# LED_PCB_LONG.net
KiCad netlist of a schematic drawn in Altium Designer
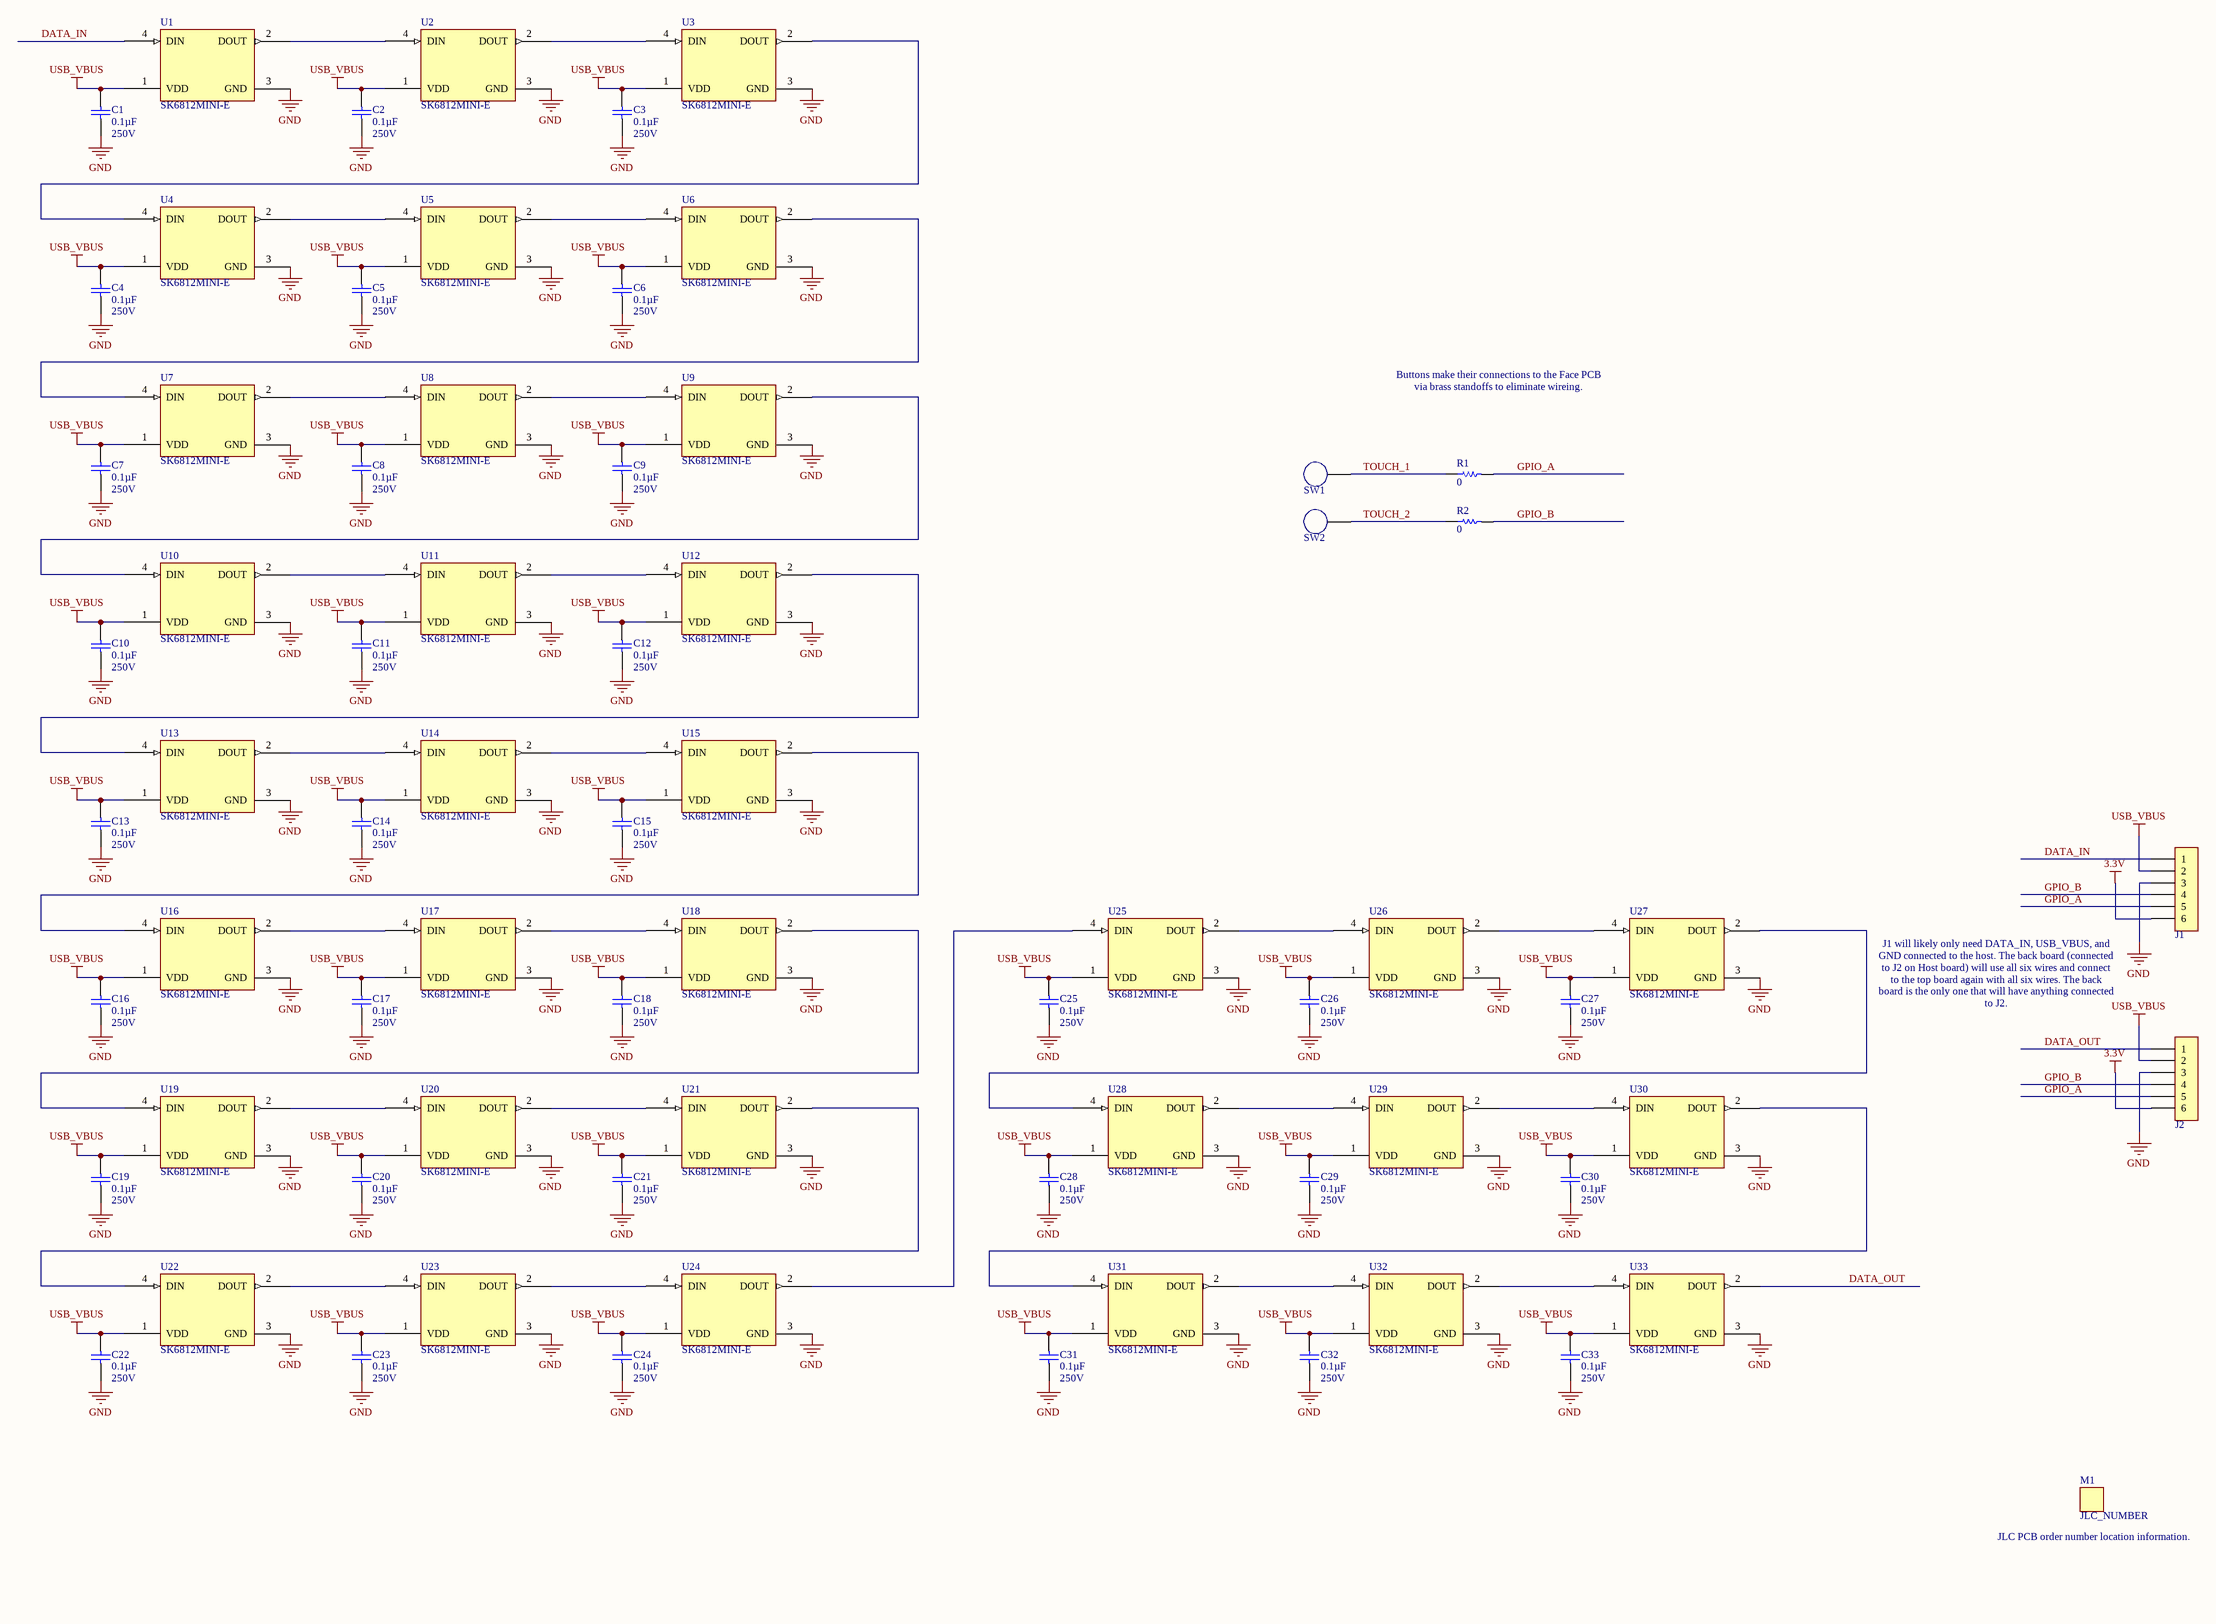
[diagram p0: LED_PCB_LONG.SchDoc]

(export (version "E")
  (design (tool "Eeschema 10.0.6"))
  (components
    (comp (ref "C1")
      (value "0.1µF")
      (footprint "Chip0805")
      (description "CAP CER 0.1UF 250V 10% X7T 0805")
      (fields
        (field (name "VOLTAGE") "250V")
        (field (name "PARTNUMBER") "C2012X7T2E104K125AA")
        (field (name "MANUFACTURER") "TDK Corporation")
      )
      (libsource (lib "Passives") (part "CAP"))
    )
    (comp (ref "C2")
      (value "0.1µF")
      (footprint "Chip0805")
      (description "CAP CER 0.1UF 250V 10% X7T 0805")
      (fields
        (field (name "VOLTAGE") "250V")
        (field (name "PARTNUMBER") "C2012X7T2E104K125AA")
        (field (name "MANUFACTURER") "TDK Corporation")
      )
      (libsource (lib "Passives") (part "CAP"))
    )
    (comp (ref "C3")
      (value "0.1µF")
      (footprint "Chip0805")
      (description "CAP CER 0.1UF 250V 10% X7T 0805")
      (fields
        (field (name "VOLTAGE") "250V")
        (field (name "PARTNUMBER") "C2012X7T2E104K125AA")
        (field (name "MANUFACTURER") "TDK Corporation")
      )
      (libsource (lib "Passives") (part "CAP"))
    )
    (comp (ref "C4")
      (value "0.1µF")
      (footprint "Chip0805")
      (description "CAP CER 0.1UF 250V 10% X7T 0805")
      (fields
        (field (name "VOLTAGE") "250V")
        (field (name "PARTNUMBER") "C2012X7T2E104K125AA")
        (field (name "MANUFACTURER") "TDK Corporation")
      )
      (libsource (lib "Passives") (part "CAP"))
    )
    (comp (ref "C5")
      (value "0.1µF")
      (footprint "Chip0805")
      (description "CAP CER 0.1UF 250V 10% X7T 0805")
      (fields
        (field (name "VOLTAGE") "250V")
        (field (name "PARTNUMBER") "C2012X7T2E104K125AA")
        (field (name "MANUFACTURER") "TDK Corporation")
      )
      (libsource (lib "Passives") (part "CAP"))
    )
    (comp (ref "C6")
      (value "0.1µF")
      (footprint "Chip0805")
      (description "CAP CER 0.1UF 250V 10% X7T 0805")
      (fields
        (field (name "VOLTAGE") "250V")
        (field (name "PARTNUMBER") "C2012X7T2E104K125AA")
        (field (name "MANUFACTURER") "TDK Corporation")
      )
      (libsource (lib "Passives") (part "CAP"))
    )
    (comp (ref "C7")
      (value "0.1µF")
      (footprint "Chip0805")
      (description "CAP CER 0.1UF 250V 10% X7T 0805")
      (fields
        (field (name "VOLTAGE") "250V")
        (field (name "PARTNUMBER") "C2012X7T2E104K125AA")
        (field (name "MANUFACTURER") "TDK Corporation")
      )
      (libsource (lib "Passives") (part "CAP"))
    )
    (comp (ref "C8")
      (value "0.1µF")
      (footprint "Chip0805")
      (description "CAP CER 0.1UF 250V 10% X7T 0805")
      (fields
        (field (name "VOLTAGE") "250V")
        (field (name "PARTNUMBER") "C2012X7T2E104K125AA")
        (field (name "MANUFACTURER") "TDK Corporation")
      )
      (libsource (lib "Passives") (part "CAP"))
    )
    (comp (ref "C9")
      (value "0.1µF")
      (footprint "Chip0805")
      (description "CAP CER 0.1UF 250V 10% X7T 0805")
      (fields
        (field (name "VOLTAGE") "250V")
        (field (name "PARTNUMBER") "C2012X7T2E104K125AA")
        (field (name "MANUFACTURER") "TDK Corporation")
      )
      (libsource (lib "Passives") (part "CAP"))
    )
    (comp (ref "C10")
      (value "0.1µF")
      (footprint "Chip0805")
      (description "CAP CER 0.1UF 250V 10% X7T 0805")
      (fields
        (field (name "VOLTAGE") "250V")
        (field (name "PARTNUMBER") "C2012X7T2E104K125AA")
        (field (name "MANUFACTURER") "TDK Corporation")
      )
      (libsource (lib "Passives") (part "CAP"))
    )
    (comp (ref "C11")
      (value "0.1µF")
      (footprint "Chip0805")
      (description "CAP CER 0.1UF 250V 10% X7T 0805")
      (fields
        (field (name "VOLTAGE") "250V")
        (field (name "PARTNUMBER") "C2012X7T2E104K125AA")
        (field (name "MANUFACTURER") "TDK Corporation")
      )
      (libsource (lib "Passives") (part "CAP"))
    )
    (comp (ref "C12")
      (value "0.1µF")
      (footprint "Chip0805")
      (description "CAP CER 0.1UF 250V 10% X7T 0805")
      (fields
        (field (name "VOLTAGE") "250V")
        (field (name "PARTNUMBER") "C2012X7T2E104K125AA")
        (field (name "MANUFACTURER") "TDK Corporation")
      )
      (libsource (lib "Passives") (part "CAP"))
    )
    (comp (ref "C13")
      (value "0.1µF")
      (footprint "Chip0805")
      (description "CAP CER 0.1UF 250V 10% X7T 0805")
      (fields
        (field (name "VOLTAGE") "250V")
        (field (name "PARTNUMBER") "C2012X7T2E104K125AA")
        (field (name "MANUFACTURER") "TDK Corporation")
      )
      (libsource (lib "Passives") (part "CAP"))
    )
    (comp (ref "C14")
      (value "0.1µF")
      (footprint "Chip0805")
      (description "CAP CER 0.1UF 250V 10% X7T 0805")
      (fields
        (field (name "VOLTAGE") "250V")
        (field (name "PARTNUMBER") "C2012X7T2E104K125AA")
        (field (name "MANUFACTURER") "TDK Corporation")
      )
      (libsource (lib "Passives") (part "CAP"))
    )
    (comp (ref "C15")
      (value "0.1µF")
      (footprint "Chip0805")
      (description "CAP CER 0.1UF 250V 10% X7T 0805")
      (fields
        (field (name "VOLTAGE") "250V")
        (field (name "PARTNUMBER") "C2012X7T2E104K125AA")
        (field (name "MANUFACTURER") "TDK Corporation")
      )
      (libsource (lib "Passives") (part "CAP"))
    )
    (comp (ref "C16")
      (value "0.1µF")
      (footprint "Chip0805")
      (description "CAP CER 0.1UF 250V 10% X7T 0805")
      (fields
        (field (name "VOLTAGE") "250V")
        (field (name "PARTNUMBER") "C2012X7T2E104K125AA")
        (field (name "MANUFACTURER") "TDK Corporation")
      )
      (libsource (lib "Passives") (part "CAP"))
    )
    (comp (ref "C17")
      (value "0.1µF")
      (footprint "Chip0805")
      (description "CAP CER 0.1UF 250V 10% X7T 0805")
      (fields
        (field (name "VOLTAGE") "250V")
        (field (name "PARTNUMBER") "C2012X7T2E104K125AA")
        (field (name "MANUFACTURER") "TDK Corporation")
      )
      (libsource (lib "Passives") (part "CAP"))
    )
    (comp (ref "C18")
      (value "0.1µF")
      (footprint "Chip0805")
      (description "CAP CER 0.1UF 250V 10% X7T 0805")
      (fields
        (field (name "VOLTAGE") "250V")
        (field (name "PARTNUMBER") "C2012X7T2E104K125AA")
        (field (name "MANUFACTURER") "TDK Corporation")
      )
      (libsource (lib "Passives") (part "CAP"))
    )
    (comp (ref "C19")
      (value "0.1µF")
      (footprint "Chip0805")
      (description "CAP CER 0.1UF 250V 10% X7T 0805")
      (fields
        (field (name "VOLTAGE") "250V")
        (field (name "PARTNUMBER") "C2012X7T2E104K125AA")
        (field (name "MANUFACTURER") "TDK Corporation")
      )
      (libsource (lib "Passives") (part "CAP"))
    )
    (comp (ref "C20")
      (value "0.1µF")
      (footprint "Chip0805")
      (description "CAP CER 0.1UF 250V 10% X7T 0805")
      (fields
        (field (name "VOLTAGE") "250V")
        (field (name "PARTNUMBER") "C2012X7T2E104K125AA")
        (field (name "MANUFACTURER") "TDK Corporation")
      )
      (libsource (lib "Passives") (part "CAP"))
    )
    (comp (ref "C21")
      (value "0.1µF")
      (footprint "Chip0805")
      (description "CAP CER 0.1UF 250V 10% X7T 0805")
      (fields
        (field (name "VOLTAGE") "250V")
        (field (name "PARTNUMBER") "C2012X7T2E104K125AA")
        (field (name "MANUFACTURER") "TDK Corporation")
      )
      (libsource (lib "Passives") (part "CAP"))
    )
    (comp (ref "C22")
      (value "0.1µF")
      (footprint "Chip0805")
      (description "CAP CER 0.1UF 250V 10% X7T 0805")
      (fields
        (field (name "VOLTAGE") "250V")
        (field (name "PARTNUMBER") "C2012X7T2E104K125AA")
        (field (name "MANUFACTURER") "TDK Corporation")
      )
      (libsource (lib "Passives") (part "CAP"))
    )
    (comp (ref "C23")
      (value "0.1µF")
      (footprint "Chip0805")
      (description "CAP CER 0.1UF 250V 10% X7T 0805")
      (fields
        (field (name "VOLTAGE") "250V")
        (field (name "PARTNUMBER") "C2012X7T2E104K125AA")
        (field (name "MANUFACTURER") "TDK Corporation")
      )
      (libsource (lib "Passives") (part "CAP"))
    )
    (comp (ref "C24")
      (value "0.1µF")
      (footprint "Chip0805")
      (description "CAP CER 0.1UF 250V 10% X7T 0805")
      (fields
        (field (name "VOLTAGE") "250V")
        (field (name "PARTNUMBER") "C2012X7T2E104K125AA")
        (field (name "MANUFACTURER") "TDK Corporation")
      )
      (libsource (lib "Passives") (part "CAP"))
    )
    (comp (ref "C25")
      (value "0.1µF")
      (footprint "Chip0805")
      (description "CAP CER 0.1UF 250V 10% X7T 0805")
      (fields
        (field (name "VOLTAGE") "250V")
        (field (name "PARTNUMBER") "C2012X7T2E104K125AA")
        (field (name "MANUFACTURER") "TDK Corporation")
      )
      (libsource (lib "Passives") (part "CAP"))
    )
    (comp (ref "C26")
      (value "0.1µF")
      (footprint "Chip0805")
      (description "CAP CER 0.1UF 250V 10% X7T 0805")
      (fields
        (field (name "VOLTAGE") "250V")
        (field (name "PARTNUMBER") "C2012X7T2E104K125AA")
        (field (name "MANUFACTURER") "TDK Corporation")
      )
      (libsource (lib "Passives") (part "CAP"))
    )
    (comp (ref "C27")
      (value "0.1µF")
      (footprint "Chip0805")
      (description "CAP CER 0.1UF 250V 10% X7T 0805")
      (fields
        (field (name "VOLTAGE") "250V")
        (field (name "PARTNUMBER") "C2012X7T2E104K125AA")
        (field (name "MANUFACTURER") "TDK Corporation")
      )
      (libsource (lib "Passives") (part "CAP"))
    )
    (comp (ref "C28")
      (value "0.1µF")
      (footprint "Chip0805")
      (description "CAP CER 0.1UF 250V 10% X7T 0805")
      (fields
        (field (name "VOLTAGE") "250V")
        (field (name "PARTNUMBER") "C2012X7T2E104K125AA")
        (field (name "MANUFACTURER") "TDK Corporation")
      )
      (libsource (lib "Passives") (part "CAP"))
    )
    (comp (ref "C29")
      (value "0.1µF")
      (footprint "Chip0805")
      (description "CAP CER 0.1UF 250V 10% X7T 0805")
      (fields
        (field (name "VOLTAGE") "250V")
        (field (name "PARTNUMBER") "C2012X7T2E104K125AA")
        (field (name "MANUFACTURER") "TDK Corporation")
      )
      (libsource (lib "Passives") (part "CAP"))
    )
    (comp (ref "C30")
      (value "0.1µF")
      (footprint "Chip0805")
      (description "CAP CER 0.1UF 250V 10% X7T 0805")
      (fields
        (field (name "VOLTAGE") "250V")
        (field (name "PARTNUMBER") "C2012X7T2E104K125AA")
        (field (name "MANUFACTURER") "TDK Corporation")
      )
      (libsource (lib "Passives") (part "CAP"))
    )
    (comp (ref "C31")
      (value "0.1µF")
      (footprint "Chip0805")
      (description "CAP CER 0.1UF 250V 10% X7T 0805")
      (fields
        (field (name "VOLTAGE") "250V")
        (field (name "PARTNUMBER") "C2012X7T2E104K125AA")
        (field (name "MANUFACTURER") "TDK Corporation")
      )
      (libsource (lib "Passives") (part "CAP"))
    )
    (comp (ref "C32")
      (value "0.1µF")
      (footprint "Chip0805")
      (description "CAP CER 0.1UF 250V 10% X7T 0805")
      (fields
        (field (name "VOLTAGE") "250V")
        (field (name "PARTNUMBER") "C2012X7T2E104K125AA")
        (field (name "MANUFACTURER") "TDK Corporation")
      )
      (libsource (lib "Passives") (part "CAP"))
    )
    (comp (ref "C33")
      (value "0.1µF")
      (footprint "Chip0805")
      (description "CAP CER 0.1UF 250V 10% X7T 0805")
      (fields
        (field (name "VOLTAGE") "250V")
        (field (name "PARTNUMBER") "C2012X7T2E104K125AA")
        (field (name "MANUFACTURER") "TDK Corporation")
      )
      (libsource (lib "Passives") (part "CAP"))
    )
    (comp (ref "J1")
      (value "HEADER_1x6_NO_BOM")
      (footprint "HEADER_1x6_100mil_NP")
      (libsource (lib "Mechanical") (part "HEADER_1x6_NO_BOM"))
    )
    (comp (ref "J2")
      (value "HEADER_1x6_NO_BOM")
      (footprint "HEADER_1x6_100mil_NP")
      (libsource (lib "Mechanical") (part "HEADER_1x6_NO_BOM"))
    )
    (comp (ref "M1")
      (value "JLC_NUMBER")
      (footprint "JLC_NUMBER")
      (description "JLC Order Number Location")
      (libsource (lib "Mechanical") (part "MECH_NO_BOM"))
    )
    (comp (ref "R1")
      (value "0")
      (footprint "Chip0805")
      (description "RES 0.0 OHM 1/8W JUMP 0805 SMD")
      (fields (field (name "PARTNUMBER") "CRCW08050000Z0EA") (field (name "MANUFACTURER") "Vishay Dale"))
      (libsource (lib "Passives") (part "RES"))
    )
    (comp (ref "R2")
      (value "0")
      (footprint "Chip0805")
      (description "RES 0.0 OHM 1/8W JUMP 0805 SMD")
      (fields (field (name "PARTNUMBER") "CRCW08050000Z0EA") (field (name "MANUFACTURER") "Vishay Dale"))
      (libsource (lib "Passives") (part "RES"))
    )
    (comp (ref "SW1")
      (value "TOUCH_PAD_NO_BOM")
      (footprint "TENTED_PAD_5mil")
      (libsource (lib "Mechanical") (part "TOUCH_PAD_NO_BOM"))
    )
    (comp (ref "SW2")
      (value "TOUCH_PAD_NO_BOM")
      (footprint "TENTED_PAD_5mil")
      (libsource (lib "Mechanical") (part "TOUCH_PAD_NO_BOM"))
    )
    (comp (ref "U1")
      (value "SK6812MINI-E")
      (footprint "SK6812MINI-E")
      (description "Addressable RGB LED")
      (fields (field (name "MANUFACTURER") "Adafruit Industries LLC"))
      (libsource (lib "Optoelectronics") (part "SK6812MINI-E"))
    )
    (comp (ref "U2")
      (value "SK6812MINI-E")
      (footprint "SK6812MINI-E")
      (description "Addressable RGB LED")
      (fields (field (name "MANUFACTURER") "Adafruit Industries LLC"))
      (libsource (lib "Optoelectronics") (part "SK6812MINI-E"))
    )
    (comp (ref "U3")
      (value "SK6812MINI-E")
      (footprint "SK6812MINI-E")
      (description "Addressable RGB LED")
      (fields (field (name "MANUFACTURER") "Adafruit Industries LLC"))
      (libsource (lib "Optoelectronics") (part "SK6812MINI-E"))
    )
    (comp (ref "U4")
      (value "SK6812MINI-E")
      (footprint "SK6812MINI-E")
      (description "Addressable RGB LED")
      (fields (field (name "MANUFACTURER") "Adafruit Industries LLC"))
      (libsource (lib "Optoelectronics") (part "SK6812MINI-E"))
    )
    (comp (ref "U5")
      (value "SK6812MINI-E")
      (footprint "SK6812MINI-E")
      (description "Addressable RGB LED")
      (fields (field (name "MANUFACTURER") "Adafruit Industries LLC"))
      (libsource (lib "Optoelectronics") (part "SK6812MINI-E"))
    )
    (comp (ref "U6")
      (value "SK6812MINI-E")
      (footprint "SK6812MINI-E")
      (description "Addressable RGB LED")
      (fields (field (name "MANUFACTURER") "Adafruit Industries LLC"))
      (libsource (lib "Optoelectronics") (part "SK6812MINI-E"))
    )
    (comp (ref "U7")
      (value "SK6812MINI-E")
      (footprint "SK6812MINI-E")
      (description "Addressable RGB LED")
      (fields (field (name "MANUFACTURER") "Adafruit Industries LLC"))
      (libsource (lib "Optoelectronics") (part "SK6812MINI-E"))
    )
    (comp (ref "U8")
      (value "SK6812MINI-E")
      (footprint "SK6812MINI-E")
      (description "Addressable RGB LED")
      (fields (field (name "MANUFACTURER") "Adafruit Industries LLC"))
      (libsource (lib "Optoelectronics") (part "SK6812MINI-E"))
    )
    (comp (ref "U9")
      (value "SK6812MINI-E")
      (footprint "SK6812MINI-E")
      (description "Addressable RGB LED")
      (fields (field (name "MANUFACTURER") "Adafruit Industries LLC"))
      (libsource (lib "Optoelectronics") (part "SK6812MINI-E"))
    )
    (comp (ref "U10")
      (value "SK6812MINI-E")
      (footprint "SK6812MINI-E")
      (description "Addressable RGB LED")
      (fields (field (name "MANUFACTURER") "Adafruit Industries LLC"))
      (libsource (lib "Optoelectronics") (part "SK6812MINI-E"))
    )
    (comp (ref "U11")
      (value "SK6812MINI-E")
      (footprint "SK6812MINI-E")
      (description "Addressable RGB LED")
      (fields (field (name "MANUFACTURER") "Adafruit Industries LLC"))
      (libsource (lib "Optoelectronics") (part "SK6812MINI-E"))
    )
    (comp (ref "U12")
      (value "SK6812MINI-E")
      (footprint "SK6812MINI-E")
      (description "Addressable RGB LED")
      (fields (field (name "MANUFACTURER") "Adafruit Industries LLC"))
      (libsource (lib "Optoelectronics") (part "SK6812MINI-E"))
    )
    (comp (ref "U13")
      (value "SK6812MINI-E")
      (footprint "SK6812MINI-E")
      (description "Addressable RGB LED")
      (fields (field (name "MANUFACTURER") "Adafruit Industries LLC"))
      (libsource (lib "Optoelectronics") (part "SK6812MINI-E"))
    )
    (comp (ref "U14")
      (value "SK6812MINI-E")
      (footprint "SK6812MINI-E")
      (description "Addressable RGB LED")
      (fields (field (name "MANUFACTURER") "Adafruit Industries LLC"))
      (libsource (lib "Optoelectronics") (part "SK6812MINI-E"))
    )
    (comp (ref "U15")
      (value "SK6812MINI-E")
      (footprint "SK6812MINI-E")
      (description "Addressable RGB LED")
      (fields (field (name "MANUFACTURER") "Adafruit Industries LLC"))
      (libsource (lib "Optoelectronics") (part "SK6812MINI-E"))
    )
    (comp (ref "U16")
      (value "SK6812MINI-E")
      (footprint "SK6812MINI-E")
      (description "Addressable RGB LED")
      (fields (field (name "MANUFACTURER") "Adafruit Industries LLC"))
      (libsource (lib "Optoelectronics") (part "SK6812MINI-E"))
    )
    (comp (ref "U17")
      (value "SK6812MINI-E")
      (footprint "SK6812MINI-E")
      (description "Addressable RGB LED")
      (fields (field (name "MANUFACTURER") "Adafruit Industries LLC"))
      (libsource (lib "Optoelectronics") (part "SK6812MINI-E"))
    )
    (comp (ref "U18")
      (value "SK6812MINI-E")
      (footprint "SK6812MINI-E")
      (description "Addressable RGB LED")
      (fields (field (name "MANUFACTURER") "Adafruit Industries LLC"))
      (libsource (lib "Optoelectronics") (part "SK6812MINI-E"))
    )
    (comp (ref "U19")
      (value "SK6812MINI-E")
      (footprint "SK6812MINI-E")
      (description "Addressable RGB LED")
      (fields (field (name "MANUFACTURER") "Adafruit Industries LLC"))
      (libsource (lib "Optoelectronics") (part "SK6812MINI-E"))
    )
    (comp (ref "U20")
      (value "SK6812MINI-E")
      (footprint "SK6812MINI-E")
      (description "Addressable RGB LED")
      (fields (field (name "MANUFACTURER") "Adafruit Industries LLC"))
      (libsource (lib "Optoelectronics") (part "SK6812MINI-E"))
    )
    (comp (ref "U21")
      (value "SK6812MINI-E")
      (footprint "SK6812MINI-E")
      (description "Addressable RGB LED")
      (fields (field (name "MANUFACTURER") "Adafruit Industries LLC"))
      (libsource (lib "Optoelectronics") (part "SK6812MINI-E"))
    )
    (comp (ref "U22")
      (value "SK6812MINI-E")
      (footprint "SK6812MINI-E")
      (description "Addressable RGB LED")
      (fields (field (name "MANUFACTURER") "Adafruit Industries LLC"))
      (libsource (lib "Optoelectronics") (part "SK6812MINI-E"))
    )
    (comp (ref "U23")
      (value "SK6812MINI-E")
      (footprint "SK6812MINI-E")
      (description "Addressable RGB LED")
      (fields (field (name "MANUFACTURER") "Adafruit Industries LLC"))
      (libsource (lib "Optoelectronics") (part "SK6812MINI-E"))
    )
    (comp (ref "U24")
      (value "SK6812MINI-E")
      (footprint "SK6812MINI-E")
      (description "Addressable RGB LED")
      (fields (field (name "MANUFACTURER") "Adafruit Industries LLC"))
      (libsource (lib "Optoelectronics") (part "SK6812MINI-E"))
    )
    (comp (ref "U25")
      (value "SK6812MINI-E")
      (footprint "SK6812MINI-E")
      (description "Addressable RGB LED")
      (fields (field (name "MANUFACTURER") "Adafruit Industries LLC"))
      (libsource (lib "Optoelectronics") (part "SK6812MINI-E"))
    )
    (comp (ref "U26")
      (value "SK6812MINI-E")
      (footprint "SK6812MINI-E")
      (description "Addressable RGB LED")
      (fields (field (name "MANUFACTURER") "Adafruit Industries LLC"))
      (libsource (lib "Optoelectronics") (part "SK6812MINI-E"))
    )
    (comp (ref "U27")
      (value "SK6812MINI-E")
      (footprint "SK6812MINI-E")
      (description "Addressable RGB LED")
      (fields (field (name "MANUFACTURER") "Adafruit Industries LLC"))
      (libsource (lib "Optoelectronics") (part "SK6812MINI-E"))
    )
    (comp (ref "U28")
      (value "SK6812MINI-E")
      (footprint "SK6812MINI-E")
      (description "Addressable RGB LED")
      (fields (field (name "MANUFACTURER") "Adafruit Industries LLC"))
      (libsource (lib "Optoelectronics") (part "SK6812MINI-E"))
    )
    (comp (ref "U29")
      (value "SK6812MINI-E")
      (footprint "SK6812MINI-E")
      (description "Addressable RGB LED")
      (fields (field (name "MANUFACTURER") "Adafruit Industries LLC"))
      (libsource (lib "Optoelectronics") (part "SK6812MINI-E"))
    )
    (comp (ref "U30")
      (value "SK6812MINI-E")
      (footprint "SK6812MINI-E")
      (description "Addressable RGB LED")
      (fields (field (name "MANUFACTURER") "Adafruit Industries LLC"))
      (libsource (lib "Optoelectronics") (part "SK6812MINI-E"))
    )
    (comp (ref "U31")
      (value "SK6812MINI-E")
      (footprint "SK6812MINI-E")
      (description "Addressable RGB LED")
      (fields (field (name "MANUFACTURER") "Adafruit Industries LLC"))
      (libsource (lib "Optoelectronics") (part "SK6812MINI-E"))
    )
    (comp (ref "U32")
      (value "SK6812MINI-E")
      (footprint "SK6812MINI-E")
      (description "Addressable RGB LED")
      (fields (field (name "MANUFACTURER") "Adafruit Industries LLC"))
      (libsource (lib "Optoelectronics") (part "SK6812MINI-E"))
    )
    (comp (ref "U33")
      (value "SK6812MINI-E")
      (footprint "SK6812MINI-E")
      (description "Addressable RGB LED")
      (fields (field (name "MANUFACTURER") "Adafruit Industries LLC"))
      (libsource (lib "Optoelectronics") (part "SK6812MINI-E"))
    )
  )
  (nets
    (net (code "1") (name "/DATA_IN") (class "Default")
      (node (ref "J1") (pin "1") (pinfunction "1_1") (pintype "passive"))
      (node (ref "U1") (pin "4") (pinfunction "DIN_4") (pintype "input"))
    )
    (net (code "2") (name "/DATA_OUT") (class "Default")
      (node (ref "J2") (pin "1") (pinfunction "1_1") (pintype "passive"))
      (node (ref "U33") (pin "2") (pinfunction "DOUT_2") (pintype "output"))
    )
    (net (code "3") (name "/GPIO_A") (class "Default")
      (node (ref "J1") (pin "5") (pinfunction "5_5") (pintype "passive"))
      (node (ref "J2") (pin "5") (pinfunction "5_5") (pintype "passive"))
      (node (ref "R1") (pin "2") (pinfunction "2_2") (pintype "passive"))
    )
    (net (code "4") (name "/GPIO_B") (class "Default")
      (node (ref "J1") (pin "4") (pinfunction "4_4") (pintype "passive"))
      (node (ref "J2") (pin "4") (pinfunction "4_4") (pintype "passive"))
      (node (ref "R2") (pin "2") (pinfunction "2_2") (pintype "passive"))
    )
    (net (code "5") (name "/TOUCH_1") (class "Default")
      (node (ref "R1") (pin "1") (pinfunction "1_1") (pintype "passive"))
      (node (ref "SW1") (pin "1") (pinfunction "1_1") (pintype "passive"))
    )
    (net (code "6") (name "/TOUCH_2") (class "Default")
      (node (ref "R2") (pin "1") (pinfunction "1_1") (pintype "passive"))
      (node (ref "SW2") (pin "1") (pinfunction "1_1") (pintype "passive"))
    )
    (net (code "7") (name "3.3V") (class "Default")
      (node (ref "J1") (pin "6") (pinfunction "6_6") (pintype "passive"))
      (node (ref "J2") (pin "6") (pinfunction "6_6") (pintype "passive"))
    )
    (net (code "8") (name "GND") (class "Default")
      (node (ref "C1") (pin "1") (pinfunction "1_1") (pintype "passive"))
      (node (ref "C10") (pin "1") (pinfunction "1_1") (pintype "passive"))
      (node (ref "C11") (pin "1") (pinfunction "1_1") (pintype "passive"))
      (node (ref "C12") (pin "1") (pinfunction "1_1") (pintype "passive"))
      (node (ref "C13") (pin "1") (pinfunction "1_1") (pintype "passive"))
      (node (ref "C14") (pin "1") (pinfunction "1_1") (pintype "passive"))
      (node (ref "C15") (pin "1") (pinfunction "1_1") (pintype "passive"))
      (node (ref "C16") (pin "1") (pinfunction "1_1") (pintype "passive"))
      (node (ref "C17") (pin "1") (pinfunction "1_1") (pintype "passive"))
      (node (ref "C18") (pin "1") (pinfunction "1_1") (pintype "passive"))
      (node (ref "C19") (pin "1") (pinfunction "1_1") (pintype "passive"))
      (node (ref "C2") (pin "1") (pinfunction "1_1") (pintype "passive"))
      (node (ref "C20") (pin "1") (pinfunction "1_1") (pintype "passive"))
      (node (ref "C21") (pin "1") (pinfunction "1_1") (pintype "passive"))
      (node (ref "C22") (pin "1") (pinfunction "1_1") (pintype "passive"))
      (node (ref "C23") (pin "1") (pinfunction "1_1") (pintype "passive"))
      (node (ref "C24") (pin "1") (pinfunction "1_1") (pintype "passive"))
      (node (ref "C25") (pin "1") (pinfunction "1_1") (pintype "passive"))
      (node (ref "C26") (pin "1") (pinfunction "1_1") (pintype "passive"))
      (node (ref "C27") (pin "1") (pinfunction "1_1") (pintype "passive"))
      (node (ref "C28") (pin "1") (pinfunction "1_1") (pintype "passive"))
      (node (ref "C29") (pin "1") (pinfunction "1_1") (pintype "passive"))
      (node (ref "C3") (pin "1") (pinfunction "1_1") (pintype "passive"))
      (node (ref "C30") (pin "1") (pinfunction "1_1") (pintype "passive"))
      (node (ref "C31") (pin "1") (pinfunction "1_1") (pintype "passive"))
      (node (ref "C32") (pin "1") (pinfunction "1_1") (pintype "passive"))
      (node (ref "C33") (pin "1") (pinfunction "1_1") (pintype "passive"))
      (node (ref "C4") (pin "1") (pinfunction "1_1") (pintype "passive"))
      (node (ref "C5") (pin "1") (pinfunction "1_1") (pintype "passive"))
      (node (ref "C6") (pin "1") (pinfunction "1_1") (pintype "passive"))
      (node (ref "C7") (pin "1") (pinfunction "1_1") (pintype "passive"))
      (node (ref "C8") (pin "1") (pinfunction "1_1") (pintype "passive"))
      (node (ref "C9") (pin "1") (pinfunction "1_1") (pintype "passive"))
      (node (ref "J1") (pin "3") (pinfunction "3_3") (pintype "passive"))
      (node (ref "J2") (pin "3") (pinfunction "3_3") (pintype "passive"))
      (node (ref "U1") (pin "3") (pinfunction "GND_3") (pintype "passive"))
      (node (ref "U10") (pin "3") (pinfunction "GND_3") (pintype "passive"))
      (node (ref "U11") (pin "3") (pinfunction "GND_3") (pintype "passive"))
      (node (ref "U12") (pin "3") (pinfunction "GND_3") (pintype "passive"))
      (node (ref "U13") (pin "3") (pinfunction "GND_3") (pintype "passive"))
      (node (ref "U14") (pin "3") (pinfunction "GND_3") (pintype "passive"))
      (node (ref "U15") (pin "3") (pinfunction "GND_3") (pintype "passive"))
      (node (ref "U16") (pin "3") (pinfunction "GND_3") (pintype "passive"))
      (node (ref "U17") (pin "3") (pinfunction "GND_3") (pintype "passive"))
      (node (ref "U18") (pin "3") (pinfunction "GND_3") (pintype "passive"))
      (node (ref "U19") (pin "3") (pinfunction "GND_3") (pintype "passive"))
      (node (ref "U2") (pin "3") (pinfunction "GND_3") (pintype "passive"))
      (node (ref "U20") (pin "3") (pinfunction "GND_3") (pintype "passive"))
      (node (ref "U21") (pin "3") (pinfunction "GND_3") (pintype "passive"))
      (node (ref "U22") (pin "3") (pinfunction "GND_3") (pintype "passive"))
      (node (ref "U23") (pin "3") (pinfunction "GND_3") (pintype "passive"))
      (node (ref "U24") (pin "3") (pinfunction "GND_3") (pintype "passive"))
      (node (ref "U25") (pin "3") (pinfunction "GND_3") (pintype "passive"))
      (node (ref "U26") (pin "3") (pinfunction "GND_3") (pintype "passive"))
      (node (ref "U27") (pin "3") (pinfunction "GND_3") (pintype "passive"))
      (node (ref "U28") (pin "3") (pinfunction "GND_3") (pintype "passive"))
      (node (ref "U29") (pin "3") (pinfunction "GND_3") (pintype "passive"))
      (node (ref "U3") (pin "3") (pinfunction "GND_3") (pintype "passive"))
      (node (ref "U30") (pin "3") (pinfunction "GND_3") (pintype "passive"))
      (node (ref "U31") (pin "3") (pinfunction "GND_3") (pintype "passive"))
      (node (ref "U32") (pin "3") (pinfunction "GND_3") (pintype "passive"))
      (node (ref "U33") (pin "3") (pinfunction "GND_3") (pintype "passive"))
      (node (ref "U4") (pin "3") (pinfunction "GND_3") (pintype "passive"))
      (node (ref "U5") (pin "3") (pinfunction "GND_3") (pintype "passive"))
      (node (ref "U6") (pin "3") (pinfunction "GND_3") (pintype "passive"))
      (node (ref "U7") (pin "3") (pinfunction "GND_3") (pintype "passive"))
      (node (ref "U8") (pin "3") (pinfunction "GND_3") (pintype "passive"))
      (node (ref "U9") (pin "3") (pinfunction "GND_3") (pintype "passive"))
    )
    (net (code "9") (name "Net-(U1-DOUT)") (class "Default")
      (node (ref "U1") (pin "2") (pinfunction "DOUT_2") (pintype "output"))
      (node (ref "U2") (pin "4") (pinfunction "DIN_4") (pintype "input"))
    )
    (net (code "10") (name "Net-(U2-DOUT)") (class "Default")
      (node (ref "U2") (pin "2") (pinfunction "DOUT_2") (pintype "output"))
      (node (ref "U3") (pin "4") (pinfunction "DIN_4") (pintype "input"))
    )
    (net (code "11") (name "Net-(U3-DOUT)") (class "Default")
      (node (ref "U3") (pin "2") (pinfunction "DOUT_2") (pintype "output"))
      (node (ref "U4") (pin "4") (pinfunction "DIN_4") (pintype "input"))
    )
    (net (code "12") (name "Net-(U4-DOUT)") (class "Default")
      (node (ref "U4") (pin "2") (pinfunction "DOUT_2") (pintype "output"))
      (node (ref "U5") (pin "4") (pinfunction "DIN_4") (pintype "input"))
    )
    (net (code "13") (name "Net-(U5-DOUT)") (class "Default")
      (node (ref "U5") (pin "2") (pinfunction "DOUT_2") (pintype "output"))
      (node (ref "U6") (pin "4") (pinfunction "DIN_4") (pintype "input"))
    )
    (net (code "14") (name "Net-(U6-DOUT)") (class "Default")
      (node (ref "U6") (pin "2") (pinfunction "DOUT_2") (pintype "output"))
      (node (ref "U7") (pin "4") (pinfunction "DIN_4") (pintype "input"))
    )
    (net (code "15") (name "Net-(U7-DOUT)") (class "Default")
      (node (ref "U7") (pin "2") (pinfunction "DOUT_2") (pintype "output"))
      (node (ref "U8") (pin "4") (pinfunction "DIN_4") (pintype "input"))
    )
    (net (code "16") (name "Net-(U8-DOUT)") (class "Default")
      (node (ref "U8") (pin "2") (pinfunction "DOUT_2") (pintype "output"))
      (node (ref "U9") (pin "4") (pinfunction "DIN_4") (pintype "input"))
    )
    (net (code "17") (name "Net-(U10-DIN)") (class "Default")
      (node (ref "U10") (pin "4") (pinfunction "DIN_4") (pintype "input"))
      (node (ref "U9") (pin "2") (pinfunction "DOUT_2") (pintype "output"))
    )
    (net (code "18") (name "Net-(U10-DOUT)") (class "Default")
      (node (ref "U10") (pin "2") (pinfunction "DOUT_2") (pintype "output"))
      (node (ref "U11") (pin "4") (pinfunction "DIN_4") (pintype "input"))
    )
    (net (code "19") (name "Net-(U11-DOUT)") (class "Default")
      (node (ref "U11") (pin "2") (pinfunction "DOUT_2") (pintype "output"))
      (node (ref "U12") (pin "4") (pinfunction "DIN_4") (pintype "input"))
    )
    (net (code "20") (name "Net-(U12-DOUT)") (class "Default")
      (node (ref "U12") (pin "2") (pinfunction "DOUT_2") (pintype "output"))
      (node (ref "U13") (pin "4") (pinfunction "DIN_4") (pintype "input"))
    )
    (net (code "21") (name "Net-(U13-DOUT)") (class "Default")
      (node (ref "U13") (pin "2") (pinfunction "DOUT_2") (pintype "output"))
      (node (ref "U14") (pin "4") (pinfunction "DIN_4") (pintype "input"))
    )
    (net (code "22") (name "Net-(U14-DOUT)") (class "Default")
      (node (ref "U14") (pin "2") (pinfunction "DOUT_2") (pintype "output"))
      (node (ref "U15") (pin "4") (pinfunction "DIN_4") (pintype "input"))
    )
    (net (code "23") (name "Net-(U15-DOUT)") (class "Default")
      (node (ref "U15") (pin "2") (pinfunction "DOUT_2") (pintype "output"))
      (node (ref "U16") (pin "4") (pinfunction "DIN_4") (pintype "input"))
    )
    (net (code "24") (name "Net-(U16-DOUT)") (class "Default")
      (node (ref "U16") (pin "2") (pinfunction "DOUT_2") (pintype "output"))
      (node (ref "U17") (pin "4") (pinfunction "DIN_4") (pintype "input"))
    )
    (net (code "25") (name "Net-(U17-DOUT)") (class "Default")
      (node (ref "U17") (pin "2") (pinfunction "DOUT_2") (pintype "output"))
      (node (ref "U18") (pin "4") (pinfunction "DIN_4") (pintype "input"))
    )
    (net (code "26") (name "Net-(U18-DOUT)") (class "Default")
      (node (ref "U18") (pin "2") (pinfunction "DOUT_2") (pintype "output"))
      (node (ref "U19") (pin "4") (pinfunction "DIN_4") (pintype "input"))
    )
    (net (code "27") (name "Net-(U19-DOUT)") (class "Default")
      (node (ref "U19") (pin "2") (pinfunction "DOUT_2") (pintype "output"))
      (node (ref "U20") (pin "4") (pinfunction "DIN_4") (pintype "input"))
    )
    (net (code "28") (name "Net-(U20-DOUT)") (class "Default")
      (node (ref "U20") (pin "2") (pinfunction "DOUT_2") (pintype "output"))
      (node (ref "U21") (pin "4") (pinfunction "DIN_4") (pintype "input"))
    )
    (net (code "29") (name "Net-(U21-DOUT)") (class "Default")
      (node (ref "U21") (pin "2") (pinfunction "DOUT_2") (pintype "output"))
      (node (ref "U22") (pin "4") (pinfunction "DIN_4") (pintype "input"))
    )
    (net (code "30") (name "Net-(U22-DOUT)") (class "Default")
      (node (ref "U22") (pin "2") (pinfunction "DOUT_2") (pintype "output"))
      (node (ref "U23") (pin "4") (pinfunction "DIN_4") (pintype "input"))
    )
    (net (code "31") (name "Net-(U23-DOUT)") (class "Default")
      (node (ref "U23") (pin "2") (pinfunction "DOUT_2") (pintype "output"))
      (node (ref "U24") (pin "4") (pinfunction "DIN_4") (pintype "input"))
    )
    (net (code "32") (name "Net-(U24-DOUT)") (class "Default")
      (node (ref "U24") (pin "2") (pinfunction "DOUT_2") (pintype "output"))
      (node (ref "U25") (pin "4") (pinfunction "DIN_4") (pintype "input"))
    )
    (net (code "33") (name "Net-(U25-DOUT)") (class "Default")
      (node (ref "U25") (pin "2") (pinfunction "DOUT_2") (pintype "output"))
      (node (ref "U26") (pin "4") (pinfunction "DIN_4") (pintype "input"))
    )
    (net (code "34") (name "Net-(U26-DOUT)") (class "Default")
      (node (ref "U26") (pin "2") (pinfunction "DOUT_2") (pintype "output"))
      (node (ref "U27") (pin "4") (pinfunction "DIN_4") (pintype "input"))
    )
    (net (code "35") (name "Net-(U27-DOUT)") (class "Default")
      (node (ref "U27") (pin "2") (pinfunction "DOUT_2") (pintype "output"))
      (node (ref "U28") (pin "4") (pinfunction "DIN_4") (pintype "input"))
    )
    (net (code "36") (name "Net-(U28-DOUT)") (class "Default")
      (node (ref "U28") (pin "2") (pinfunction "DOUT_2") (pintype "output"))
      (node (ref "U29") (pin "4") (pinfunction "DIN_4") (pintype "input"))
    )
    (net (code "37") (name "Net-(U29-DOUT)") (class "Default")
      (node (ref "U29") (pin "2") (pinfunction "DOUT_2") (pintype "output"))
      (node (ref "U30") (pin "4") (pinfunction "DIN_4") (pintype "input"))
    )
    (net (code "38") (name "Net-(U30-DOUT)") (class "Default")
      (node (ref "U30") (pin "2") (pinfunction "DOUT_2") (pintype "output"))
      (node (ref "U31") (pin "4") (pinfunction "DIN_4") (pintype "input"))
    )
    (net (code "39") (name "Net-(U31-DOUT)") (class "Default")
      (node (ref "U31") (pin "2") (pinfunction "DOUT_2") (pintype "output"))
      (node (ref "U32") (pin "4") (pinfunction "DIN_4") (pintype "input"))
    )
    (net (code "40") (name "Net-(U32-DOUT)") (class "Default")
      (node (ref "U32") (pin "2") (pinfunction "DOUT_2") (pintype "output"))
      (node (ref "U33") (pin "4") (pinfunction "DIN_4") (pintype "input"))
    )
    (net (code "41") (name "USB_VBUS") (class "Default")
      (node (ref "C1") (pin "2") (pinfunction "2_2") (pintype "passive"))
      (node (ref "C10") (pin "2") (pinfunction "2_2") (pintype "passive"))
      (node (ref "C11") (pin "2") (pinfunction "2_2") (pintype "passive"))
      (node (ref "C12") (pin "2") (pinfunction "2_2") (pintype "passive"))
      (node (ref "C13") (pin "2") (pinfunction "2_2") (pintype "passive"))
      (node (ref "C14") (pin "2") (pinfunction "2_2") (pintype "passive"))
      (node (ref "C15") (pin "2") (pinfunction "2_2") (pintype "passive"))
      (node (ref "C16") (pin "2") (pinfunction "2_2") (pintype "passive"))
      (node (ref "C17") (pin "2") (pinfunction "2_2") (pintype "passive"))
      (node (ref "C18") (pin "2") (pinfunction "2_2") (pintype "passive"))
      (node (ref "C19") (pin "2") (pinfunction "2_2") (pintype "passive"))
      (node (ref "C2") (pin "2") (pinfunction "2_2") (pintype "passive"))
      (node (ref "C20") (pin "2") (pinfunction "2_2") (pintype "passive"))
      (node (ref "C21") (pin "2") (pinfunction "2_2") (pintype "passive"))
      (node (ref "C22") (pin "2") (pinfunction "2_2") (pintype "passive"))
      (node (ref "C23") (pin "2") (pinfunction "2_2") (pintype "passive"))
      (node (ref "C24") (pin "2") (pinfunction "2_2") (pintype "passive"))
      (node (ref "C25") (pin "2") (pinfunction "2_2") (pintype "passive"))
      (node (ref "C26") (pin "2") (pinfunction "2_2") (pintype "passive"))
      (node (ref "C27") (pin "2") (pinfunction "2_2") (pintype "passive"))
      (node (ref "C28") (pin "2") (pinfunction "2_2") (pintype "passive"))
      (node (ref "C29") (pin "2") (pinfunction "2_2") (pintype "passive"))
      (node (ref "C3") (pin "2") (pinfunction "2_2") (pintype "passive"))
      (node (ref "C30") (pin "2") (pinfunction "2_2") (pintype "passive"))
      (node (ref "C31") (pin "2") (pinfunction "2_2") (pintype "passive"))
      (node (ref "C32") (pin "2") (pinfunction "2_2") (pintype "passive"))
      (node (ref "C33") (pin "2") (pinfunction "2_2") (pintype "passive"))
      (node (ref "C4") (pin "2") (pinfunction "2_2") (pintype "passive"))
      (node (ref "C5") (pin "2") (pinfunction "2_2") (pintype "passive"))
      (node (ref "C6") (pin "2") (pinfunction "2_2") (pintype "passive"))
      (node (ref "C7") (pin "2") (pinfunction "2_2") (pintype "passive"))
      (node (ref "C8") (pin "2") (pinfunction "2_2") (pintype "passive"))
      (node (ref "C9") (pin "2") (pinfunction "2_2") (pintype "passive"))
      (node (ref "J1") (pin "2") (pinfunction "2_2") (pintype "passive"))
      (node (ref "J2") (pin "2") (pinfunction "2_2") (pintype "passive"))
      (node (ref "U1") (pin "1") (pinfunction "VDD_1") (pintype "passive"))
      (node (ref "U10") (pin "1") (pinfunction "VDD_1") (pintype "passive"))
      (node (ref "U11") (pin "1") (pinfunction "VDD_1") (pintype "passive"))
      (node (ref "U12") (pin "1") (pinfunction "VDD_1") (pintype "passive"))
      (node (ref "U13") (pin "1") (pinfunction "VDD_1") (pintype "passive"))
      (node (ref "U14") (pin "1") (pinfunction "VDD_1") (pintype "passive"))
      (node (ref "U15") (pin "1") (pinfunction "VDD_1") (pintype "passive"))
      (node (ref "U16") (pin "1") (pinfunction "VDD_1") (pintype "passive"))
      (node (ref "U17") (pin "1") (pinfunction "VDD_1") (pintype "passive"))
      (node (ref "U18") (pin "1") (pinfunction "VDD_1") (pintype "passive"))
      (node (ref "U19") (pin "1") (pinfunction "VDD_1") (pintype "passive"))
      (node (ref "U2") (pin "1") (pinfunction "VDD_1") (pintype "passive"))
      (node (ref "U20") (pin "1") (pinfunction "VDD_1") (pintype "passive"))
      (node (ref "U21") (pin "1") (pinfunction "VDD_1") (pintype "passive"))
      (node (ref "U22") (pin "1") (pinfunction "VDD_1") (pintype "passive"))
      (node (ref "U23") (pin "1") (pinfunction "VDD_1") (pintype "passive"))
      (node (ref "U24") (pin "1") (pinfunction "VDD_1") (pintype "passive"))
      (node (ref "U25") (pin "1") (pinfunction "VDD_1") (pintype "passive"))
      (node (ref "U26") (pin "1") (pinfunction "VDD_1") (pintype "passive"))
      (node (ref "U27") (pin "1") (pinfunction "VDD_1") (pintype "passive"))
      (node (ref "U28") (pin "1") (pinfunction "VDD_1") (pintype "passive"))
      (node (ref "U29") (pin "1") (pinfunction "VDD_1") (pintype "passive"))
      (node (ref "U3") (pin "1") (pinfunction "VDD_1") (pintype "passive"))
      (node (ref "U30") (pin "1") (pinfunction "VDD_1") (pintype "passive"))
      (node (ref "U31") (pin "1") (pinfunction "VDD_1") (pintype "passive"))
      (node (ref "U32") (pin "1") (pinfunction "VDD_1") (pintype "passive"))
      (node (ref "U33") (pin "1") (pinfunction "VDD_1") (pintype "passive"))
      (node (ref "U4") (pin "1") (pinfunction "VDD_1") (pintype "passive"))
      (node (ref "U5") (pin "1") (pinfunction "VDD_1") (pintype "passive"))
      (node (ref "U6") (pin "1") (pinfunction "VDD_1") (pintype "passive"))
      (node (ref "U7") (pin "1") (pinfunction "VDD_1") (pintype "passive"))
      (node (ref "U8") (pin "1") (pinfunction "VDD_1") (pintype "passive"))
      (node (ref "U9") (pin "1") (pinfunction "VDD_1") (pintype "passive"))
    )
  )
)
